# J-Link_Cortex_with_VCOM_Adapter.net
KiCad netlist of a schematic drawn in Altium Designer
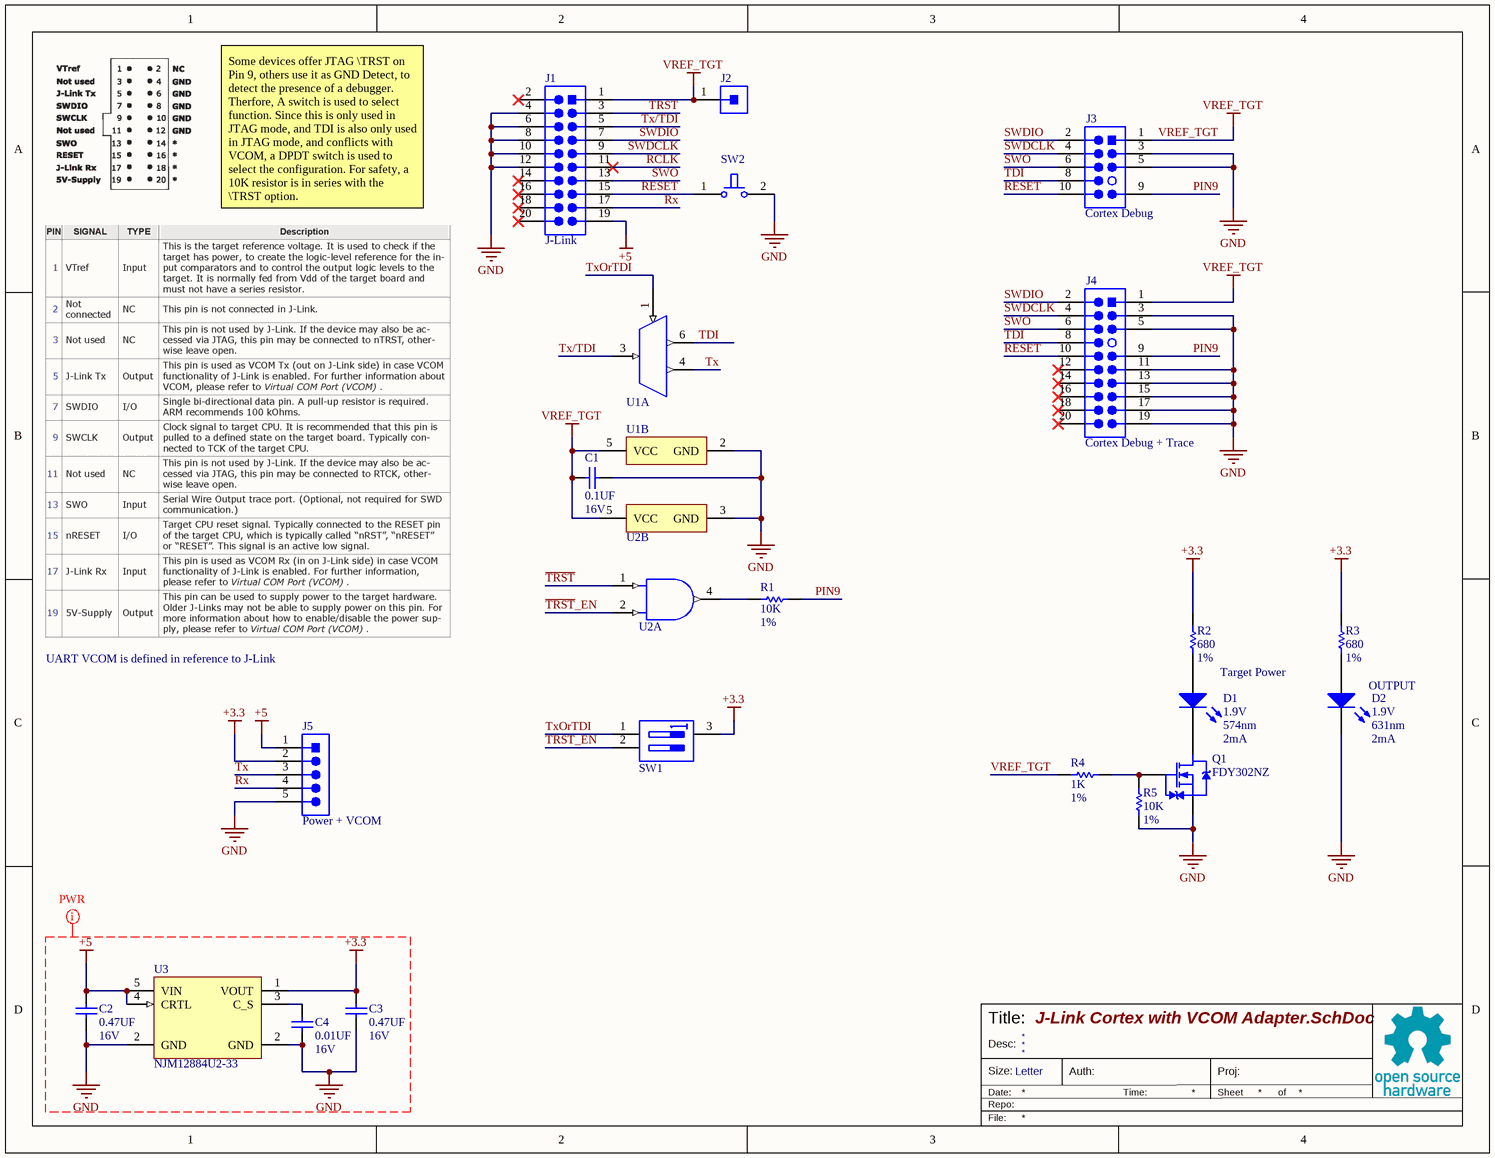
[diagram p0: J-Link Cortex with VCOM Adapter.SchDoc]

(export (version "E")
  (design (tool "Eeschema 10.0.6"))
  (components
    (comp (ref "C1")
      (value "CAP 0603 0.1UF 16V 10% X7R")
      (footprint "0603_CAP")
      (description "Capacitor Surface Mount 0603 Footprint 0.1UF 16V 10% Tolerance Ceramic X7R")
      (fields
        (field (name "VAL") "0.1UF")
        (field (name "VOL") "16V")
        (field (name "MANUFACTURER") "Various")
        (field (name "VOLTAGE") "16V")
      )
      (libsource (lib "Passive Components") (part "cap"))
    )
    (comp (ref "C2")
      (value "CAP 0603 0.47UF 16V 10% X7R")
      (footprint "0603_CAP")
      (description "Capacitor Surface Mount 0603 Footprint 0.47UF 16V 10% Tolerance Ceramic X7R")
      (fields
        (field (name "VAL") "0.47UF")
        (field (name "VOL") "16V")
        (field (name "MANUFACTURER") "Various")
        (field (name "VOLTAGE") "16V")
      )
      (libsource (lib "Passive Components") (part "cap"))
    )
    (comp (ref "C3")
      (value "CAP 0603 0.47UF 16V 10% X7R")
      (footprint "0603_CAP")
      (description "Capacitor Surface Mount 0603 Footprint 0.47UF 16V 10% Tolerance Ceramic X7R")
      (fields
        (field (name "VAL") "0.47UF")
        (field (name "VOL") "16V")
        (field (name "MANUFACTURER") "Various")
        (field (name "VOLTAGE") "16V")
      )
      (libsource (lib "Passive Components") (part "cap"))
    )
    (comp (ref "C4")
      (value "CAP 0603 0.01UF 16V 10% X7R")
      (footprint "0603_CAP")
      (description "Capacitor Surface Mount 0603 Footprint 0.01UF 16V 10% Tolerance Ceramic X7R")
      (fields
        (field (name "VAL") "0.01UF")
        (field (name "VOL") "16V")
        (field (name "MANUFACTURER") "Various")
        (field (name "VOLTAGE") "16V")
      )
      (libsource (lib "Passive Components") (part "cap"))
    )
    (comp (ref "D1")
      (value "Green LED")
      (footprint "SM0805GCL")
      (description "Green 574nm LED Indication - Discrete 1.9V 0805 (2012 Metric)")
      (fields
        (field (name "MANUFACTURER") "Bivar")
        (field (name "VOLTAGE RATING") "1.9V")
        (field (name "WAVELENGTH") "574nm")
        (field (name "TEST CURRENT") "2mA")
      )
      (libsource (lib "Discrete Semiconductors") (part "LED_Single"))
    )
    (comp (ref "D2")
      (value "Red LED")
      (footprint "SM0805HCL")
      (description "Red 631nm LED Indication - Discrete 1.9V 0805 (2012 Metric)")
      (fields
        (field (name "MANUFACTURER") "Bivar")
        (field (name "VOLTAGE RATING") "1.9V")
        (field (name "WAVELENGTH") "631nm")
        (field (name "TEST CURRENT") "2mA")
      )
      (libsource (lib "Discrete Semiconductors") (part "LED_Single"))
    )
    (comp (ref "J1")
      (value "20 contact Female header, RA")
      (footprint "SFH11-PBPC-D10-RA-BK")
      (description "20 Position Header Connector  Through Hole, Right Angle")
      (fields (field (name "MANUFACTURER") "Sullins"))
      (libsource (lib "Connectors") (part "Header 10X2"))
    )
    (comp (ref "J2")
      (value "1 contacts Male header")
      (footprint "PH1-01-UA round pad with connector")
      (description "Connector Male Header 1X1 vertical 1contact 0.100in pitch Gold finish TH")
      (fields (field (name "MANUFACTURER") "Adam Tech"))
      (libsource (lib "Connectors") (part "Header 1X1"))
    )
    (comp (ref "J3")
      (value "Cortex Debug, 0.050\" 10 Pin")
      (footprint "FTSH-105-01-F-DV-007-K PLUGOUT")
      (description "10 Pin Shrouded Header, 0.050\", Key Pin 7")
      (fields (field (name "MANUFACTURER") "Samtech"))
      (libsource (lib "Connectors") (part "Cortex Debug"))
    )
    (comp (ref "J4")
      (value "Cortex Debug+ETM Connector, 0.050\" 20 Pin")
      (footprint "FTSH-110-01-F-DV-007-K plugout")
      (description "20 Pin Shrouded Header, 0.050\", Key Pin 7")
      (fields (field (name "MANUFACTURER") "Samtech"))
      (libsource (lib "Connectors") (part "Cortex Trace"))
    )
    (comp (ref "J5")
      (value "5 contacts Male header")
      (footprint "70543-0109 - slim")
      (description "Connector Male Header 1X5 vertical 5contacts 0.100in pitch 0.76um Gold finish shrouded with latch")
      (fields (field (name "MANUFACTURER") "Molex"))
      (libsource (lib "Connectors") (part "Header 1X5"))
    )
    (comp (ref "Q1")
      (value "N-Channel MOSFET")
      (footprint "SC89")
      (description "N-Channel 20V 600mA (Ta) 625mW (Ta) Surface Mount SC-89")
      (fields (field (name "MANUFACTURER P/N") "FDY302NZ") (field (name "MANUFACTURER") "On Semiconductor"))
      (libsource (lib "Discrete Semiconductors") (part "N_Channel_SC89_ESD"))
    )
    (comp (ref "R1")
      (value "RES 0603 10K 1%")
      (footprint "0603_RES")
      (description "Resistor Surface Mount, 10K Ohms, 0603 Footprint, 1% Tolerance 0.1W")
      (fields
        (field (name "VAL") "10K")
        (field (name "TOL") "1%")
        (field (name "MANUFACTURER") "Various")
        (field (name "TOLERANCE") "1%")
      )
      (libsource (lib "Passive Components") (part "res"))
    )
    (comp (ref "R2")
      (value "RES 0603 680 1%")
      (footprint "0603_RES")
      (description "Resistor Surface Mount, 680 Ohms, 0603 Footprint, 1% Tolerance 0.1W")
      (fields
        (field (name "VAL") "680")
        (field (name "TOL") "1%")
        (field (name "MANUFACTURER") "Various")
        (field (name "TOLERANCE") "1%")
      )
      (libsource (lib "Passive Components") (part "res"))
    )
    (comp (ref "R3")
      (value "RES 0603 680 1%")
      (footprint "0603_RES")
      (description "Resistor Surface Mount, 680 Ohms, 0603 Footprint, 1% Tolerance 0.1W")
      (fields
        (field (name "VAL") "680")
        (field (name "TOL") "1%")
        (field (name "MANUFACTURER") "Various")
        (field (name "TOLERANCE") "1%")
      )
      (libsource (lib "Passive Components") (part "res"))
    )
    (comp (ref "R4")
      (value "RES 0603 1K 1%")
      (footprint "0603_RES")
      (description "Resistor Surface Mount, 1K Ohms, 0603 Footprint, 1% Tolerance 0.1W")
      (fields
        (field (name "VAL") "1K")
        (field (name "TOL") "1%")
        (field (name "MANUFACTURER") "Various")
        (field (name "TOLERANCE") "1%")
      )
      (libsource (lib "Passive Components") (part "res"))
    )
    (comp (ref "R5")
      (value "RES 0603 10K 1%")
      (footprint "0603_RES")
      (description "Resistor Surface Mount, 10K Ohms, 0603 Footprint, 1% Tolerance 0.1W")
      (fields
        (field (name "VAL") "10K")
        (field (name "TOL") "1%")
        (field (name "MANUFACTURER") "Various")
        (field (name "TOLERANCE") "1%")
      )
      (libsource (lib "Passive Components") (part "res"))
    )
    (comp (ref "SW1")
      (value "SWITCH SLIDE DIP SPST 10MA 20V")
      (footprint "SPA02B")
      (description "Dip Switch SPST 2 Position Through Hole Slide (Standard) Actuator 10mA 20VDC, Commoned")
      (fields (field (name "MANUFACTURER") "C&K"))
      (libsource (lib "Electromechanical") (part "SPA02B"))
    )
    (comp (ref "SW2")
      (value "SWITCH TACTILE SPST-NO 0.02A 15V")
      (footprint "EVP-BB2A9B000 LOW DENSITY")
      (description "Tactile Switch SPST-NO Top Actuated Surface Mount")
      (fields (field (name "MANUFACTURER") "Panasonic Electronic Components"))
      (libsource (lib "Electromechanical") (part "SPST-MOM-2"))
    )
    (comp (ref "U1")
      (value "Demultiplexer")
      (footprint "SOT363")
      (description "Single 1-of-2 Non-Inverting Demultiplexer with 3-State Deselected Output SC70-6")
      (fields (field (name "MANUFACTURER") "Texas Instruments"))
      (libsource (lib "Integrated Circuits") (part "SN74LVC1G18_DBV/DCK/DRY/DSF"))
    )
    (comp (ref "U2")
      (value "Single AND Gate")
      (footprint "SOT353")
      (description "Single Positive-AND Gate SMT 2-Input SOT-353")
      (fields (field (name "MANUFACTURER") "Texas Instruments"))
      (libsource (lib "Integrated Circuits") (part "SN74AHC1G08"))
    )
    (comp (ref "U3")
      (value "3.3V LDO Soft start reverse current reverse voltage")
      (footprint "SOT89-5_NJR")
      (description "Linear Voltage Regulator IC  1 Output  500mA SOT-89-5")
      (fields (field (name "P/N") "NJM12884U2-33") (field (name "MANUFACTURER") "NJR Corporation/NJRC"))
      (libsource (lib "Integrated Circuits") (part "NJM12884U2"))
    )
  )
  (nets
    (net (code "1") (name "+3.3") (class "Default")
      (node (ref "C3") (pin "2") (pinfunction "2_2") (pintype "passive"))
      (node (ref "J5") (pin "2") (pinfunction "2_2") (pintype "passive"))
      (node (ref "R2") (pin "2") (pinfunction "2_2") (pintype "passive"))
      (node (ref "R3") (pin "2") (pinfunction "2_2") (pintype "passive"))
      (node (ref "SW1") (pin "3") (pinfunction "COM_3") (pintype "passive"))
      (node (ref "U3") (pin "1") (pinfunction "VOUT_1") (pintype "power_in"))
    )
    (net (code "2") (name "+5") (class "Default")
      (node (ref "C2") (pin "2") (pinfunction "2_2") (pintype "passive"))
      (node (ref "J1") (pin "19") (pinfunction "19_19") (pintype "passive"))
      (node (ref "J5") (pin "1") (pinfunction "1_1") (pintype "passive"))
      (node (ref "U3") (pin "4") (pinfunction "CRTL_4") (pintype "input"))
      (node (ref "U3") (pin "5") (pinfunction "VIN_5") (pintype "power_in"))
    )
    (net (code "3") (name "/PIN9") (class "Default")
      (node (ref "J3") (pin "9") (pinfunction "GNDDetect_9") (pintype "passive"))
      (node (ref "J4") (pin "9") (pinfunction "GNDDetect_9") (pintype "passive"))
      (node (ref "R1") (pin "1") (pinfunction "1_1") (pintype "passive"))
    )
    (net (code "4") (name "/RCLK") (class "Default")
      (node (ref "J1") (pin "11") (pinfunction "11_11") (pintype "passive+no_connect"))
    )
    (net (code "5") (name "/RESET") (class "Default")
      (node (ref "J1") (pin "15") (pinfunction "15_15") (pintype "passive"))
      (node (ref "J3") (pin "10") (pinfunction "RESET_10") (pintype "passive"))
      (node (ref "J4") (pin "10") (pinfunction "RESET_10") (pintype "passive"))
      (node (ref "SW2") (pin "1") (pinfunction "1_1") (pintype "passive"))
    )
    (net (code "6") (name "/Rx") (class "Default")
      (node (ref "J1") (pin "17") (pinfunction "17_17") (pintype "passive"))
      (node (ref "J5") (pin "4") (pinfunction "4_4") (pintype "passive"))
    )
    (net (code "7") (name "/SWDCLK") (class "Default")
      (node (ref "J1") (pin "9") (pinfunction "9_9") (pintype "passive"))
      (node (ref "J3") (pin "4") (pinfunction "SWDCLK/TCK_4") (pintype "passive"))
      (node (ref "J4") (pin "4") (pinfunction "SWDCLK/TCK_4") (pintype "passive"))
    )
    (net (code "8") (name "/SWDIO") (class "Default")
      (node (ref "J1") (pin "7") (pinfunction "7_7") (pintype "passive"))
      (node (ref "J3") (pin "2") (pinfunction "SWDIO/TMS_2") (pintype "passive"))
      (node (ref "J4") (pin "2") (pinfunction "SWDIO/TMS_2") (pintype "passive"))
    )
    (net (code "9") (name "/SWO") (class "Default")
      (node (ref "J1") (pin "13") (pinfunction "13_13") (pintype "passive"))
      (node (ref "J3") (pin "6") (pinfunction "SWO/TDO_6") (pintype "passive"))
      (node (ref "J4") (pin "6") (pinfunction "SWO/TDO/EXTa/TRACECTL_6") (pintype "passive"))
    )
    (net (code "10") (name "/TDI") (class "Default")
      (node (ref "J3") (pin "8") (pinfunction "NC/TDI_8") (pintype "passive"))
      (node (ref "J4") (pin "8") (pinfunction "NC/EXTb/TDI_8") (pintype "passive"))
      (node (ref "U1") (pin "6") (pinfunction "Y0_6") (pintype "output"))
    )
    (net (code "11") (name "/TRST") (class "Default")
      (node (ref "J1") (pin "3") (pinfunction "3_3") (pintype "passive"))
      (node (ref "U2") (pin "1") (pinfunction "A_1") (pintype "input"))
    )
    (net (code "12") (name "/Tx") (class "Default")
      (node (ref "J5") (pin "3") (pinfunction "3_3") (pintype "passive"))
      (node (ref "U1") (pin "4") (pinfunction "Y1_4") (pintype "output"))
    )
    (net (code "13") (name "/TxOrTDI") (class "Default")
      (node (ref "SW1") (pin "1") (pinfunction "1_1") (pintype "passive"))
      (node (ref "U1") (pin "1") (pinfunction "S_1") (pintype "input"))
    )
    (net (code "14") (name "/Tx{slash}TDI") (class "Default")
      (node (ref "J1") (pin "5") (pinfunction "5_5") (pintype "passive"))
      (node (ref "U1") (pin "3") (pinfunction "A_3") (pintype "input"))
    )
    (net (code "15") (name "/~{TRST}_EN") (class "Default")
      (node (ref "SW1") (pin "2") (pinfunction "2_2") (pintype "passive"))
      (node (ref "U2") (pin "2") (pinfunction "B_2") (pintype "input"))
    )
    (net (code "16") (name "GND") (class "Default")
      (node (ref "C1") (pin "2") (pinfunction "2_2") (pintype "passive"))
      (node (ref "C2") (pin "1") (pinfunction "1_1") (pintype "passive"))
      (node (ref "C3") (pin "1") (pinfunction "1_1") (pintype "passive"))
      (node (ref "C4") (pin "1") (pinfunction "1_1") (pintype "passive"))
      (node (ref "D2") (pin "K") (pinfunction "K_K") (pintype "passive"))
      (node (ref "J1") (pin "10") (pinfunction "10_10") (pintype "passive"))
      (node (ref "J1") (pin "12") (pinfunction "12_12") (pintype "passive"))
      (node (ref "J1") (pin "4") (pinfunction "4_4") (pintype "passive"))
      (node (ref "J1") (pin "6") (pinfunction "6_6") (pintype "passive"))
      (node (ref "J1") (pin "8") (pinfunction "8_8") (pintype "passive"))
      (node (ref "J3") (pin "3") (pinfunction "GND_3") (pintype "power_in"))
      (node (ref "J3") (pin "5") (pinfunction "GND_5") (pintype "power_in"))
      (node (ref "J4") (pin "11") (pinfunction "GND/TgtPwr+Cap_11") (pintype "passive"))
      (node (ref "J4") (pin "13") (pinfunction "13_13") (pintype "power_in"))
      (node (ref "J4") (pin "15") (pinfunction "GND_15") (pintype "power_in"))
      (node (ref "J4") (pin "17") (pinfunction "GND_17") (pintype "power_in"))
      (node (ref "J4") (pin "19") (pinfunction "GND_19") (pintype "power_in"))
      (node (ref "J4") (pin "3") (pinfunction "GND_3") (pintype "power_in"))
      (node (ref "J4") (pin "5") (pinfunction "GND_5") (pintype "power_in"))
      (node (ref "J5") (pin "5") (pinfunction "5_5") (pintype "passive"))
      (node (ref "Q1") (pin "2") (pinfunction "S_2") (pintype "passive"))
      (node (ref "R5") (pin "1") (pinfunction "1_1") (pintype "passive"))
      (node (ref "SW2") (pin "2") (pinfunction "2_2") (pintype "passive"))
      (node (ref "U1") (pin "2") (pinfunction "GND_2") (pintype "power_in"))
      (node (ref "U2") (pin "3") (pinfunction "GND_3") (pintype "power_in"))
      (node (ref "U3") (pin "2") (pinfunction "GND_2") (pintype "power_in"))
    )
    (net (code "17") (name "Net-(D1-PadA)") (class "Default")
      (node (ref "D1") (pin "A") (pinfunction "A_A") (pintype "passive"))
      (node (ref "R2") (pin "1") (pinfunction "1_1") (pintype "passive"))
    )
    (net (code "18") (name "Net-(D2-PadA)") (class "Default")
      (node (ref "D2") (pin "A") (pinfunction "A_A") (pintype "passive"))
      (node (ref "R3") (pin "1") (pinfunction "1_1") (pintype "passive"))
    )
    (net (code "19") (name "Net-(Q1-D)") (class "Default")
      (node (ref "D1") (pin "K") (pinfunction "K_K") (pintype "passive"))
      (node (ref "Q1") (pin "3") (pinfunction "D_3") (pintype "passive"))
    )
    (net (code "20") (name "Net-(Q1-G)") (class "Default")
      (node (ref "Q1") (pin "1") (pinfunction "G_1") (pintype "passive"))
      (node (ref "R4") (pin "2") (pinfunction "2_2") (pintype "passive"))
      (node (ref "R5") (pin "2") (pinfunction "2_2") (pintype "passive"))
    )
    (net (code "21") (name "Net-(U2A-Y)") (class "Default")
      (node (ref "R1") (pin "2") (pinfunction "2_2") (pintype "passive"))
      (node (ref "U2") (pin "4") (pinfunction "Y_4") (pintype "output"))
    )
    (net (code "22") (name "Net-(U3-C_S)") (class "Default")
      (node (ref "C4") (pin "2") (pinfunction "2_2") (pintype "passive"))
      (node (ref "U3") (pin "3") (pinfunction "C_S_3") (pintype "passive"))
    )
    (net (code "23") (name "VREF_TGT") (class "Default")
      (node (ref "C1") (pin "1") (pinfunction "1_1") (pintype "passive"))
      (node (ref "J1") (pin "1") (pinfunction "1_1") (pintype "passive"))
      (node (ref "J2") (pin "1") (pinfunction "1_1") (pintype "passive"))
      (node (ref "J3") (pin "1") (pinfunction "VCC_1") (pintype "power_in"))
      (node (ref "J4") (pin "1") (pinfunction "VCC_1") (pintype "power_in"))
      (node (ref "R4") (pin "1") (pinfunction "1_1") (pintype "passive"))
      (node (ref "U1") (pin "5") (pinfunction "VCC_5") (pintype "power_in"))
      (node (ref "U2") (pin "5") (pinfunction "VCC_5") (pintype "power_in"))
    )
    (net (code "24") (name "unconnected-(J1-Pad2)") (class "Default")
      (node (ref "J1") (pin "2") (pinfunction "2_2") (pintype "passive+no_connect"))
    )
    (net (code "25") (name "unconnected-(J1-Pad14)") (class "Default")
      (node (ref "J1") (pin "14") (pinfunction "14_14") (pintype "passive+no_connect"))
    )
    (net (code "26") (name "unconnected-(J1-Pad16)") (class "Default")
      (node (ref "J1") (pin "16") (pinfunction "16_16") (pintype "passive+no_connect"))
    )
    (net (code "27") (name "unconnected-(J1-Pad18)") (class "Default")
      (node (ref "J1") (pin "18") (pinfunction "18_18") (pintype "passive+no_connect"))
    )
    (net (code "28") (name "unconnected-(J1-Pad20)") (class "Default")
      (node (ref "J1") (pin "20") (pinfunction "20_20") (pintype "passive+no_connect"))
    )
    (net (code "29") (name "unconnected-(J4-TRACECLK-Pad12)") (class "Default")
      (node (ref "J4") (pin "12") (pinfunction "TRACECLK_12") (pintype "passive+no_connect"))
    )
    (net (code "30") (name "unconnected-(J4-TRACEDATA[0]-Pad14)") (class "Default")
      (node (ref "J4") (pin "14") (pinfunction "TRACEDATA[0]_14") (pintype "passive+no_connect"))
    )
    (net (code "31") (name "unconnected-(J4-TRACEDATA[1]-Pad16)") (class "Default")
      (node (ref "J4") (pin "16") (pinfunction "TRACEDATA[1]_16") (pintype "passive+no_connect"))
    )
    (net (code "32") (name "unconnected-(J4-TRACEDATA[2]-Pad18)") (class "Default")
      (node (ref "J4") (pin "18") (pinfunction "TRACEDATA[2]_18") (pintype "passive+no_connect"))
    )
    (net (code "33") (name "unconnected-(J4-TRACEDATA[3]-Pad20)") (class "Default")
      (node (ref "J4") (pin "20") (pinfunction "TRACEDATA[3]_20") (pintype "passive+no_connect"))
    )
  )
)
